# Power_Supply.net
KiCad netlist of a schematic drawn in Altium Designer
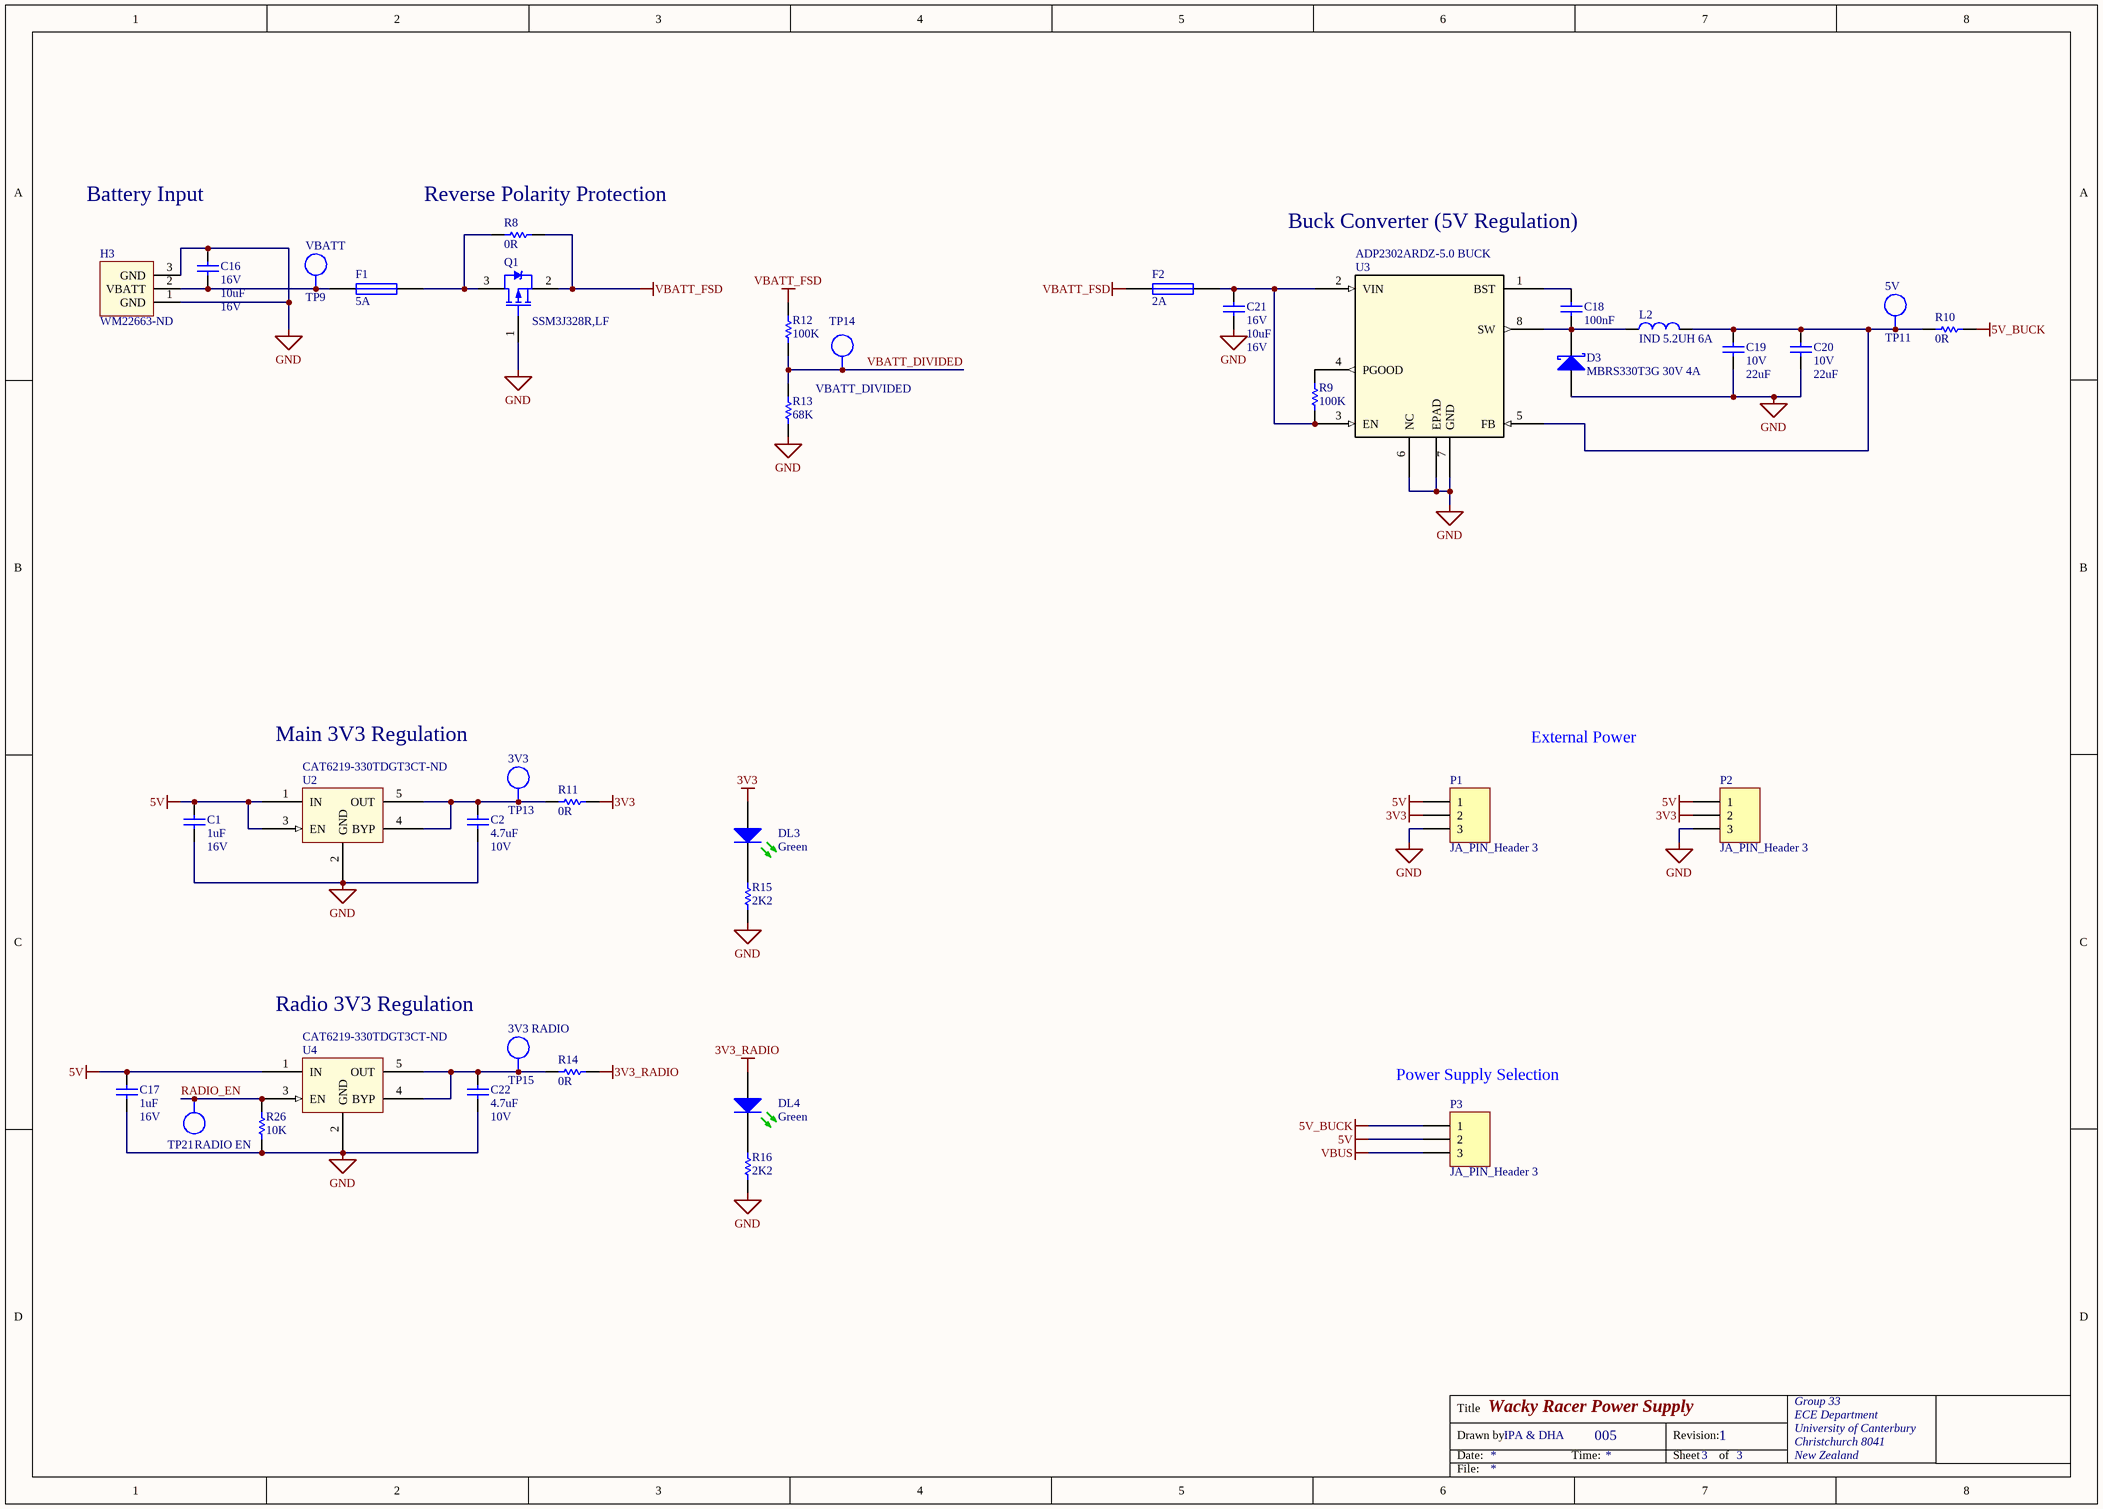
[diagram p0: Power_Supply.SchDoc]

(export (version "E")
  (design (tool "Eeschema 10.0.6"))
  (components
    (comp (ref "C1")
      (value "1uF")
      (footprint "CAPC1608L")
      (description "CAP CER 1uF Y5V -20% +80% 16V 0603")
      (fields (field (name "MAX VOLTAGE") "16V"))
      (libsource (lib "ECE_ComponentsAD23") (part "CC_1uF_0603"))
    )
    (comp (ref "C2")
      (value "4.7uF")
      (footprint "CAPC1608N")
      (description "CAP CER 4.7uF X5R +-20%  10V 0603")
      (fields (field (name "MAX VOLTAGE") "10V"))
      (libsource (lib "ECE_ComponentsAD23") (part "CC_4.7uF_0603"))
    )
    (comp (ref "C16")
      (value "10uF")
      (footprint "CAPC2012L")
      (description "CAP CER 10uF X5R 16V 0805")
      (fields
        (field (name "MANUFACTURER") "Samsung Electro-Mechanics")
        (field (name "MANUFACTURER PART NUMBER") "CL21A106KOQNNWE")
        (field (name "VOLTAGE - RATED") "16V")
        (field (name "MAX VOLTAGE") "16V")
      )
      (libsource (lib "ECE_ComponentsAD23") (part "CC_10uF_0805_16V"))
    )
    (comp (ref "C17")
      (value "1uF")
      (footprint "CAPC1608L")
      (description "CAP CER 1uF Y5V -20% +80% 16V 0603")
      (fields (field (name "MAX VOLTAGE") "16V"))
      (libsource (lib "ECE_ComponentsAD23") (part "CC_1uF_0603"))
    )
    (comp (ref "C18")
      (value "100nF")
      (footprint "CAPC1608L")
      (description "CAP CER 100nF X7R +-10% 50V 0603")
      (libsource (lib "ECE_ComponentsAD23") (part "CC_100nF_0603"))
    )
    (comp (ref "C19")
      (value "22uF")
      (footprint "CAPC3216L")
      (description "CAP CER 22uF Y5V -20% +80% 10V 1206")
      (fields (field (name "MAX VOLTAGE") "10V"))
      (libsource (lib "ECE_ComponentsAD23") (part "CC_22uF_1206"))
    )
    (comp (ref "C20")
      (value "22uF")
      (footprint "CAPC3216L")
      (description "CAP CER 22uF Y5V -20% +80% 10V 1206")
      (fields (field (name "MAX VOLTAGE") "10V"))
      (libsource (lib "ECE_ComponentsAD23") (part "CC_22uF_1206"))
    )
    (comp (ref "C21")
      (value "10uF")
      (footprint "CAPC2012L")
      (description "CAP CER 10uF X5R 16V 0805")
      (fields
        (field (name "MANUFACTURER") "Samsung Electro-Mechanics")
        (field (name "MANUFACTURER PART NUMBER") "CL21A106KOQNNWE")
        (field (name "VOLTAGE - RATED") "16V")
        (field (name "MAX VOLTAGE") "16V")
      )
      (libsource (lib "ECE_ComponentsAD23") (part "CC_10uF_0805_16V"))
    )
    (comp (ref "C22")
      (value "4.7uF")
      (footprint "CAPC1608N")
      (description "CAP CER 4.7uF X5R +-20%  10V 0603")
      (fields (field (name "MAX VOLTAGE") "10V"))
      (libsource (lib "ECE_ComponentsAD23") (part "CC_4.7uF_0603"))
    )
    (comp (ref "D3")
      (value "MBRS330T3G 30V 4A")
      (footprint "SMC")
      (description "SCHOTTKY  30V 4A")
      (fields
        (field (name "MANUFACTURER") "ON Semiconductor")
        (field (name "MANUFACTURER PART NUMBER") "MBRS330T3G")
      )
      (libsource (lib "ENCE461AD23") (part "MBRS330T3G"))
    )
    (comp (ref "DL3")
      (value "Green")
      (footprint "WL-SMCW0603")
      (description "LED Green 430mcd 0603 SMD")
      (fields
        (field (name "MANUFACTURER") "WURTH ELEKTRONIK")
        (field (name "MANUFACTURER PART NUMBER") "150060GS75000")
        (field (name "LED COLOUR") "Green")
      )
      (libsource (lib "ECE_ComponentsAD23") (part "DL_150060GS75000"))
    )
    (comp (ref "DL4")
      (value "Green")
      (footprint "WL-SMCW0603")
      (description "LED Green 430mcd 0603 SMD")
      (fields
        (field (name "MANUFACTURER") "WURTH ELEKTRONIK")
        (field (name "MANUFACTURER PART NUMBER") "150060GS75000")
        (field (name "LED COLOUR") "Green")
      )
      (libsource (lib "ECE_ComponentsAD23") (part "DL_150060GS75000"))
    )
    (comp (ref "F1")
      (value "5A")
      (footprint "RESC3216N")
      (description "Fuse 5.0A Fast Acting 1206 SMD")
      (fields (field (name "MANUFACTURER PART NUMBER") "C1F5") (field (name "MANUFACTURER") "Bel TRP"))
      (libsource (lib "ECE_ComponentsAD23") (part "FS_Fuse_5.0A"))
    )
    (comp (ref "F2")
      (value "2A")
      (footprint "RESC3216N")
      (description "Fuse 2.0A Very Fast Acting 1206 SMD")
      (fields
        (field (name "MANUFACTURER") "MULTICOMP")
        (field (name "MANUFACTURER PART NUMBER") "MC12CF 002")
      )
      (libsource (lib "ECE_ComponentsAD23") (part "FS_Fuse_2.0A"))
    )
    (comp (ref "H3")
      (value "Battery_HEADER_3pin")
      (footprint "BATT_HEADER_3POS")
      (description "3Pin Header 2.54mm spacing\r\nDigikey #WM22663-ND")
      (fields (field (name "SUPPLIER PART NUMBER 1") "WM22663-ND"))
      (libsource (lib "ENCE461AD23") (part "Battery_HEADER_3pin"))
    )
    (comp (ref "L2")
      (value "IND 5.2UH 6A")
      (footprint "INDUCTOR5u2")
      (description "FIXED IND 5.2UH 6A 22 MOHM SMD")
      (fields
        (field (name "MANUFACTURER") "Sumida America Components Inc.")
        (field (name "MANUFACTURER PART NUMBER") "CDRH104RNP-5R2NC")
      )
      (libsource (lib "ENCE461AD23") (part "CDRH104RNP-5R2NC"))
    )
    (comp (ref "P1")
      (value "JA_PIN_Header 3")
      (footprint "HDR1X3")
      (description "Header, 3-Pin")
      (fields (field (name "PUBLISHER") "Altium Limited"))
      (libsource (lib "ECE_ComponentsAD23") (part "JA_PIN_Header 3"))
    )
    (comp (ref "P2")
      (value "JA_PIN_Header 3")
      (footprint "HDR1X3")
      (description "Header, 3-Pin")
      (fields (field (name "PUBLISHER") "Altium Limited"))
      (libsource (lib "ECE_ComponentsAD23") (part "JA_PIN_Header 3"))
    )
    (comp (ref "P3")
      (value "JA_PIN_Header 3")
      (footprint "HDR1X3")
      (description "Header, 3-Pin")
      (fields (field (name "PUBLISHER") "Altium Limited"))
      (libsource (lib "ECE_ComponentsAD23") (part "JA_PIN_Header 3"))
    )
    (comp (ref "Q1")
      (value "SSM3J328R,LF")
      (footprint "SOT23_L")
      (description "MOSFET P-CH 20V 6A SOT23-3")
      (fields
        (field (name "MANUFACTURER") "Toshiba")
        (field (name "MANUFACTURER PART NUMBER") "SSM3J328R,LF")
      )
      (libsource (lib "ECE_ComponentsAD23") (part "TM_SSM3J328R"))
    )
    (comp (ref "R8")
      (value "0R")
      (footprint "RESC1608L")
      (description "RES 0.0 OHM 1/10W 5% 0603 SMD")
      (libsource (lib "ECE_ComponentsAD23") (part "RS_0R0"))
    )
    (comp (ref "R9")
      (value "100K")
      (footprint "RESC1608L")
      (description "RES 100K OHM 1/10W 5% 0603 SMD")
      (libsource (lib "ECE_ComponentsAD23") (part "RS_100K"))
    )
    (comp (ref "R10")
      (value "0R")
      (footprint "RESC1608L")
      (description "RES 0.0 OHM 1/10W 5% 0603 SMD")
      (libsource (lib "ECE_ComponentsAD23") (part "RS_0R0"))
    )
    (comp (ref "R11")
      (value "0R")
      (footprint "RESC1608L")
      (description "RES 0.0 OHM 1/10W 5% 0603 SMD")
      (libsource (lib "ECE_ComponentsAD23") (part "RS_0R0"))
    )
    (comp (ref "R12")
      (value "100K")
      (footprint "RESC1608L")
      (description "RES 100K OHM 1/10W 5% 0603 SMD")
      (libsource (lib "ECE_ComponentsAD23") (part "RS_100K"))
    )
    (comp (ref "R13")
      (value "68K")
      (footprint "RESC1608L")
      (description "RES 68.0K OHM 1/10W 5% 0603 SMD")
      (libsource (lib "ECE_ComponentsAD23") (part "RS_68K"))
    )
    (comp (ref "R14")
      (value "0R")
      (footprint "RESC1608L")
      (description "RES 0.0 OHM 1/10W 5% 0603 SMD")
      (libsource (lib "ECE_ComponentsAD23") (part "RS_0R0"))
    )
    (comp (ref "R15")
      (value "2K2")
      (footprint "RESC1608L")
      (description "RES 2.2K OHM 1/10W 5% 0603 SMD")
      (libsource (lib "ECE_ComponentsAD23") (part "RS_2K2"))
    )
    (comp (ref "R16")
      (value "2K2")
      (footprint "RESC1608L")
      (description "RES 2.2K OHM 1/10W 5% 0603 SMD")
      (libsource (lib "ECE_ComponentsAD23") (part "RS_2K2"))
    )
    (comp (ref "R26")
      (value "10K")
      (footprint "RESC1608L")
      (description "RES 10.0K OHM 1/10W 5% 0603 SMD")
      (libsource (lib "ECE_ComponentsAD23") (part "RS_10K"))
    )
    (comp (ref "TP9")
      (value "VBATT")
      (footprint "TP_1206")
      (description "Test-Point 3.3x1.6x2.1mm SMD")
      (fields
        (field (name "MANUFACTURER") "Harwin Inc")
        (field (name "MANUFACTURER PART NUMBER") "S1751-46R")
      )
      (libsource (lib "ECE_ComponentsAD23") (part "TP_1206"))
    )
    (comp (ref "TP11")
      (value "5V")
      (footprint "TP_1206")
      (description "Test-Point 3.3x1.6x2.1mm SMD")
      (fields
        (field (name "MANUFACTURER") "Harwin Inc")
        (field (name "MANUFACTURER PART NUMBER") "S1751-46R")
      )
      (libsource (lib "ECE_ComponentsAD23") (part "TP_1206"))
    )
    (comp (ref "TP13")
      (value "3V3")
      (footprint "TP_1206")
      (description "Test-Point 3.3x1.6x2.1mm SMD")
      (fields
        (field (name "MANUFACTURER") "Harwin Inc")
        (field (name "MANUFACTURER PART NUMBER") "S1751-46R")
      )
      (libsource (lib "ECE_ComponentsAD23") (part "TP_1206"))
    )
    (comp (ref "TP14")
      (value "VBATT_DIVIDED")
      (footprint "TP_1206")
      (description "Test-Point 3.3x1.6x2.1mm SMD")
      (fields
        (field (name "MANUFACTURER") "Harwin Inc")
        (field (name "MANUFACTURER PART NUMBER") "S1751-46R")
      )
      (libsource (lib "ECE_ComponentsAD23") (part "TP_1206"))
    )
    (comp (ref "TP15")
      (value "3V3 RADIO")
      (footprint "TP_1206")
      (description "Test-Point 3.3x1.6x2.1mm SMD")
      (fields
        (field (name "MANUFACTURER") "Harwin Inc")
        (field (name "MANUFACTURER PART NUMBER") "S1751-46R")
      )
      (libsource (lib "ECE_ComponentsAD23") (part "TP_1206"))
    )
    (comp (ref "TP21")
      (value "RADIO EN")
      (footprint "TP_1206")
      (description "Test-Point 3.3x1.6x2.1mm SMD")
      (fields
        (field (name "MANUFACTURER") "Harwin Inc")
        (field (name "MANUFACTURER PART NUMBER") "S1751-46R")
      )
      (libsource (lib "ECE_ComponentsAD23") (part "TP_1206"))
    )
    (comp (ref "U2")
      (value "CAT6219-330TDGT3")
      (footprint "SOT95P280X145-5N")
      (description "IC REG LIN 3.3V 500MA TSOT23-5")
      (fields
        (field (name "BASE PART NUMBER") "CAT6219")
        (field (name "SUPPLIER PART NUMBER") "CAT6219-330TDGT3CT-ND")
      )
      (libsource (lib "ENCE461AD23") (part "SV_CAT6219-330TDGT3"))
    )
    (comp (ref "U3")
      (value "ADP2302ARDZ-5.0 BUCK")
      (footprint "RD_8_1")
      (description "IC REG BUCK 5V 2A 8SOIC")
      (fields (field (name "MANUFACTURER_PART_NUMBER") "ADP2302ARDZ-5.0-R7"))
      (libsource (lib "ENCE461AD23") (part "ADP2302ARDZ-5.0-R7"))
    )
    (comp (ref "U4")
      (value "CAT6219-330TDGT3")
      (footprint "SOT95P280X145-5N")
      (description "IC REG LIN 3.3V 500MA TSOT23-5")
      (fields
        (field (name "BASE PART NUMBER") "CAT6219")
        (field (name "SUPPLIER PART NUMBER") "CAT6219-330TDGT3CT-ND")
      )
      (libsource (lib "ENCE461AD23") (part "SV_CAT6219-330TDGT3"))
    )
  )
  (nets
    (net (code "1") (name "/RADIO_EN") (class "Default")
      (node (ref "R26") (pin "2") (pinfunction "2_2") (pintype "passive"))
      (node (ref "TP21") (pin "1") (pinfunction "1_1") (pintype "passive"))
      (node (ref "U4") (pin "3") (pinfunction "EN_3") (pintype "input"))
    )
    (net (code "2") (name "/VBATT_DIVIDED") (class "Default")
      (node (ref "R12") (pin "1") (pinfunction "1_1") (pintype "passive"))
      (node (ref "R13") (pin "2") (pinfunction "2_2") (pintype "passive"))
      (node (ref "TP14") (pin "1") (pinfunction "1_1") (pintype "passive"))
    )
    (net (code "3") (name "3V3") (class "Default")
      (node (ref "DL3") (pin "2") (pinfunction "A_2") (pintype "passive"))
      (node (ref "P1") (pin "2") (pinfunction "2_2") (pintype "passive"))
      (node (ref "P2") (pin "2") (pinfunction "2_2") (pintype "passive"))
      (node (ref "R11") (pin "2") (pinfunction "2_2") (pintype "passive"))
    )
    (net (code "4") (name "3V3_RADIO") (class "Default")
      (node (ref "DL4") (pin "2") (pinfunction "A_2") (pintype "passive"))
      (node (ref "R14") (pin "2") (pinfunction "2_2") (pintype "passive"))
    )
    (net (code "5") (name "5V") (class "Default")
      (node (ref "C1") (pin "1") (pinfunction "1_1") (pintype "passive"))
      (node (ref "C17") (pin "1") (pinfunction "1_1") (pintype "passive"))
      (node (ref "P1") (pin "1") (pinfunction "1_1") (pintype "passive"))
      (node (ref "P2") (pin "1") (pinfunction "1_1") (pintype "passive"))
      (node (ref "P3") (pin "2") (pinfunction "2_2") (pintype "passive"))
      (node (ref "U2") (pin "1") (pinfunction "IN_1") (pintype "power_in"))
      (node (ref "U2") (pin "3") (pinfunction "EN_3") (pintype "input"))
      (node (ref "U4") (pin "1") (pinfunction "IN_1") (pintype "power_in"))
    )
    (net (code "6") (name "5V_BUCK") (class "Default")
      (node (ref "P3") (pin "1") (pinfunction "1_1") (pintype "passive"))
      (node (ref "R10") (pin "2") (pinfunction "2_2") (pintype "passive"))
    )
    (net (code "7") (name "GND") (class "Default")
      (node (ref "C1") (pin "2") (pinfunction "2_2") (pintype "passive"))
      (node (ref "C16") (pin "2") (pinfunction "2_2") (pintype "passive"))
      (node (ref "C17") (pin "2") (pinfunction "2_2") (pintype "passive"))
      (node (ref "C19") (pin "1") (pinfunction "1_1") (pintype "passive"))
      (node (ref "C2") (pin "1") (pinfunction "1_1") (pintype "passive"))
      (node (ref "C20") (pin "1") (pinfunction "1_1") (pintype "passive"))
      (node (ref "C21") (pin "1") (pinfunction "1_1") (pintype "passive"))
      (node (ref "C22") (pin "1") (pinfunction "1_1") (pintype "passive"))
      (node (ref "D3") (pin "1") (pinfunction "A_1") (pintype "passive"))
      (node (ref "H3") (pin "1") (pinfunction "GND_1") (pintype "passive"))
      (node (ref "H3") (pin "3") (pinfunction "GND_3") (pintype "passive"))
      (node (ref "P1") (pin "3") (pinfunction "3_3") (pintype "passive"))
      (node (ref "P2") (pin "3") (pinfunction "3_3") (pintype "passive"))
      (node (ref "Q1") (pin "1") (pinfunction "1_1") (pintype "passive"))
      (node (ref "R13") (pin "1") (pinfunction "1_1") (pintype "passive"))
      (node (ref "R15") (pin "1") (pinfunction "1_1") (pintype "passive"))
      (node (ref "R16") (pin "1") (pinfunction "1_1") (pintype "passive"))
      (node (ref "R26") (pin "1") (pinfunction "1_1") (pintype "passive"))
      (node (ref "U2") (pin "2") (pinfunction "GND_2") (pintype "power_in"))
      (node (ref "U3") (pin "6") (pinfunction "NC_6") (pintype "passive"))
      (node (ref "U3") (pin "7") (pinfunction "GND_7") (pintype "power_in"))
      (node (ref "U3") (pin "EPAD") (pinfunction "EPAD_EPAD") (pintype "passive"))
      (node (ref "U4") (pin "2") (pinfunction "GND_2") (pintype "power_in"))
    )
    (net (code "8") (name "Net-(D3-K)") (class "Default")
      (node (ref "C18") (pin "1") (pinfunction "1_1") (pintype "passive"))
      (node (ref "D3") (pin "2") (pinfunction "K_2") (pintype "passive"))
      (node (ref "L2") (pin "1") (pintype "passive"))
      (node (ref "U3") (pin "8") (pinfunction "SW_8") (pintype "output"))
    )
    (net (code "9") (name "Net-(DL3-K)") (class "Default")
      (node (ref "DL3") (pin "1") (pinfunction "K_1") (pintype "passive"))
      (node (ref "R15") (pin "2") (pinfunction "2_2") (pintype "passive"))
    )
    (net (code "10") (name "Net-(DL4-K)") (class "Default")
      (node (ref "DL4") (pin "1") (pinfunction "K_1") (pintype "passive"))
      (node (ref "R16") (pin "2") (pinfunction "2_2") (pintype "passive"))
    )
    (net (code "11") (name "Net-(F1-Pad2)") (class "Default")
      (node (ref "F1") (pin "2") (pinfunction "2_2") (pintype "passive"))
      (node (ref "Q1") (pin "3") (pinfunction "3_3") (pintype "passive"))
      (node (ref "R8") (pin "1") (pinfunction "1_1") (pintype "passive"))
    )
    (net (code "12") (name "Net-(H3-VBATT)") (class "Default")
      (node (ref "C16") (pin "1") (pinfunction "1_1") (pintype "passive"))
      (node (ref "F1") (pin "1") (pinfunction "1_1") (pintype "passive"))
      (node (ref "H3") (pin "2") (pinfunction "VBATT_2") (pintype "passive"))
      (node (ref "TP9") (pin "1") (pinfunction "1_1") (pintype "passive"))
    )
    (net (code "13") (name "Net-(U2-BYP)") (class "Default")
      (node (ref "C2") (pin "2") (pinfunction "2_2") (pintype "passive"))
      (node (ref "R11") (pin "1") (pinfunction "1_1") (pintype "passive"))
      (node (ref "TP13") (pin "1") (pinfunction "1_1") (pintype "passive"))
      (node (ref "U2") (pin "4") (pinfunction "BYP_4") (pintype "passive"))
      (node (ref "U2") (pin "5") (pinfunction "OUT_5") (pintype "power_in"))
    )
    (net (code "14") (name "Net-(U3-BST)") (class "Default")
      (node (ref "C18") (pin "2") (pinfunction "2_2") (pintype "passive"))
      (node (ref "U3") (pin "1") (pinfunction "BST_1") (pintype "passive"))
    )
    (net (code "15") (name "Net-(U3-EN)") (class "Default")
      (node (ref "C21") (pin "2") (pinfunction "2_2") (pintype "passive"))
      (node (ref "F2") (pin "2") (pinfunction "2_2") (pintype "passive"))
      (node (ref "R9") (pin "1") (pinfunction "1_1") (pintype "passive"))
      (node (ref "U3") (pin "2") (pinfunction "VIN_2") (pintype "input"))
      (node (ref "U3") (pin "3") (pinfunction "EN_3") (pintype "input"))
    )
    (net (code "16") (name "Net-(U3-FB)") (class "Default")
      (node (ref "C19") (pin "2") (pinfunction "2_2") (pintype "passive"))
      (node (ref "C20") (pin "2") (pinfunction "2_2") (pintype "passive"))
      (node (ref "L2") (pin "2") (pintype "passive"))
      (node (ref "R10") (pin "1") (pinfunction "1_1") (pintype "passive"))
      (node (ref "TP11") (pin "1") (pinfunction "1_1") (pintype "passive"))
      (node (ref "U3") (pin "5") (pinfunction "FB_5") (pintype "input"))
    )
    (net (code "17") (name "Net-(U3-PGOOD)") (class "Default")
      (node (ref "R9") (pin "2") (pinfunction "2_2") (pintype "passive"))
      (node (ref "U3") (pin "4") (pinfunction "PGOOD_4") (pintype "output"))
    )
    (net (code "18") (name "Net-(U4-BYP)") (class "Default")
      (node (ref "C22") (pin "2") (pinfunction "2_2") (pintype "passive"))
      (node (ref "R14") (pin "1") (pinfunction "1_1") (pintype "passive"))
      (node (ref "TP15") (pin "1") (pinfunction "1_1") (pintype "passive"))
      (node (ref "U4") (pin "4") (pinfunction "BYP_4") (pintype "passive"))
      (node (ref "U4") (pin "5") (pinfunction "OUT_5") (pintype "power_in"))
    )
    (net (code "19") (name "VBATT_FSD") (class "Default")
      (node (ref "F2") (pin "1") (pinfunction "1_1") (pintype "passive"))
      (node (ref "Q1") (pin "2") (pinfunction "2_2") (pintype "passive"))
      (node (ref "R12") (pin "2") (pinfunction "2_2") (pintype "passive"))
      (node (ref "R8") (pin "2") (pinfunction "2_2") (pintype "passive"))
    )
    (net (code "20") (name "VBUS") (class "Default")
      (node (ref "P3") (pin "3") (pinfunction "3_3") (pintype "passive"))
    )
  )
)
